# MUX.net
KiCad netlist of a schematic drawn in Altium Designer
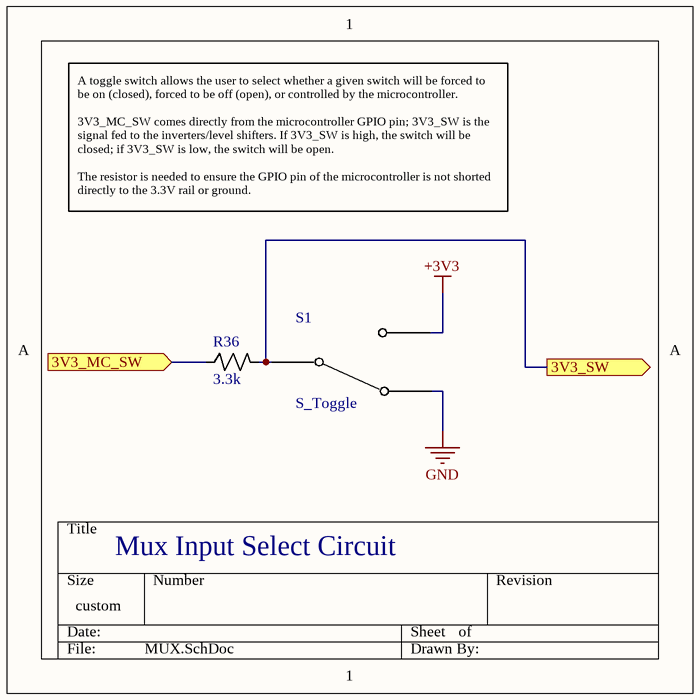
[diagram p0: MUX.SchDoc]

(export (version "E")
  (design (tool "Eeschema 10.0.6"))
  (components
    (comp (ref "R36")
      (value "3.3k")
      (footprint "0603_RES")
      (description "Resistor 3.3 kOhm 0603 1%")
      (libsource (lib "Load_Bank_New_IntLib") (part "R_3300Ohm_0603_1%"))
    )
    (comp (ref "S1")
      (value "S_Toggle")
      (footprint "TOGGLE")
      (description "Switch Toggle")
      (libsource (lib "Load_Bank_New_IntLib") (part "S_Toggle"))
    )
  )
  (nets
    (net (code "1") (name "+3V3") (class "Default")
      (node (ref "S1") (pin "3") (pinfunction "3_3") (pintype "passive"))
    )
    (net (code "2") (name "/3V3_MC_SW") (class "Default") (node (ref "R36") (pin "1") (pintype "passive")))
    (net (code "3") (name "/3V3_SW") (class "Default")
      (node (ref "R36") (pin "2") (pintype "passive"))
      (node (ref "S1") (pin "2") (pinfunction "2_2") (pintype "passive"))
    )
    (net (code "4") (name "GND") (class "Default")
      (node (ref "S1") (pin "1") (pinfunction "1_1") (pintype "passive"))
    )
  )
)
